# 1_ZynTra-Power.net
KiCad netlist of a schematic drawn in Altium Designer
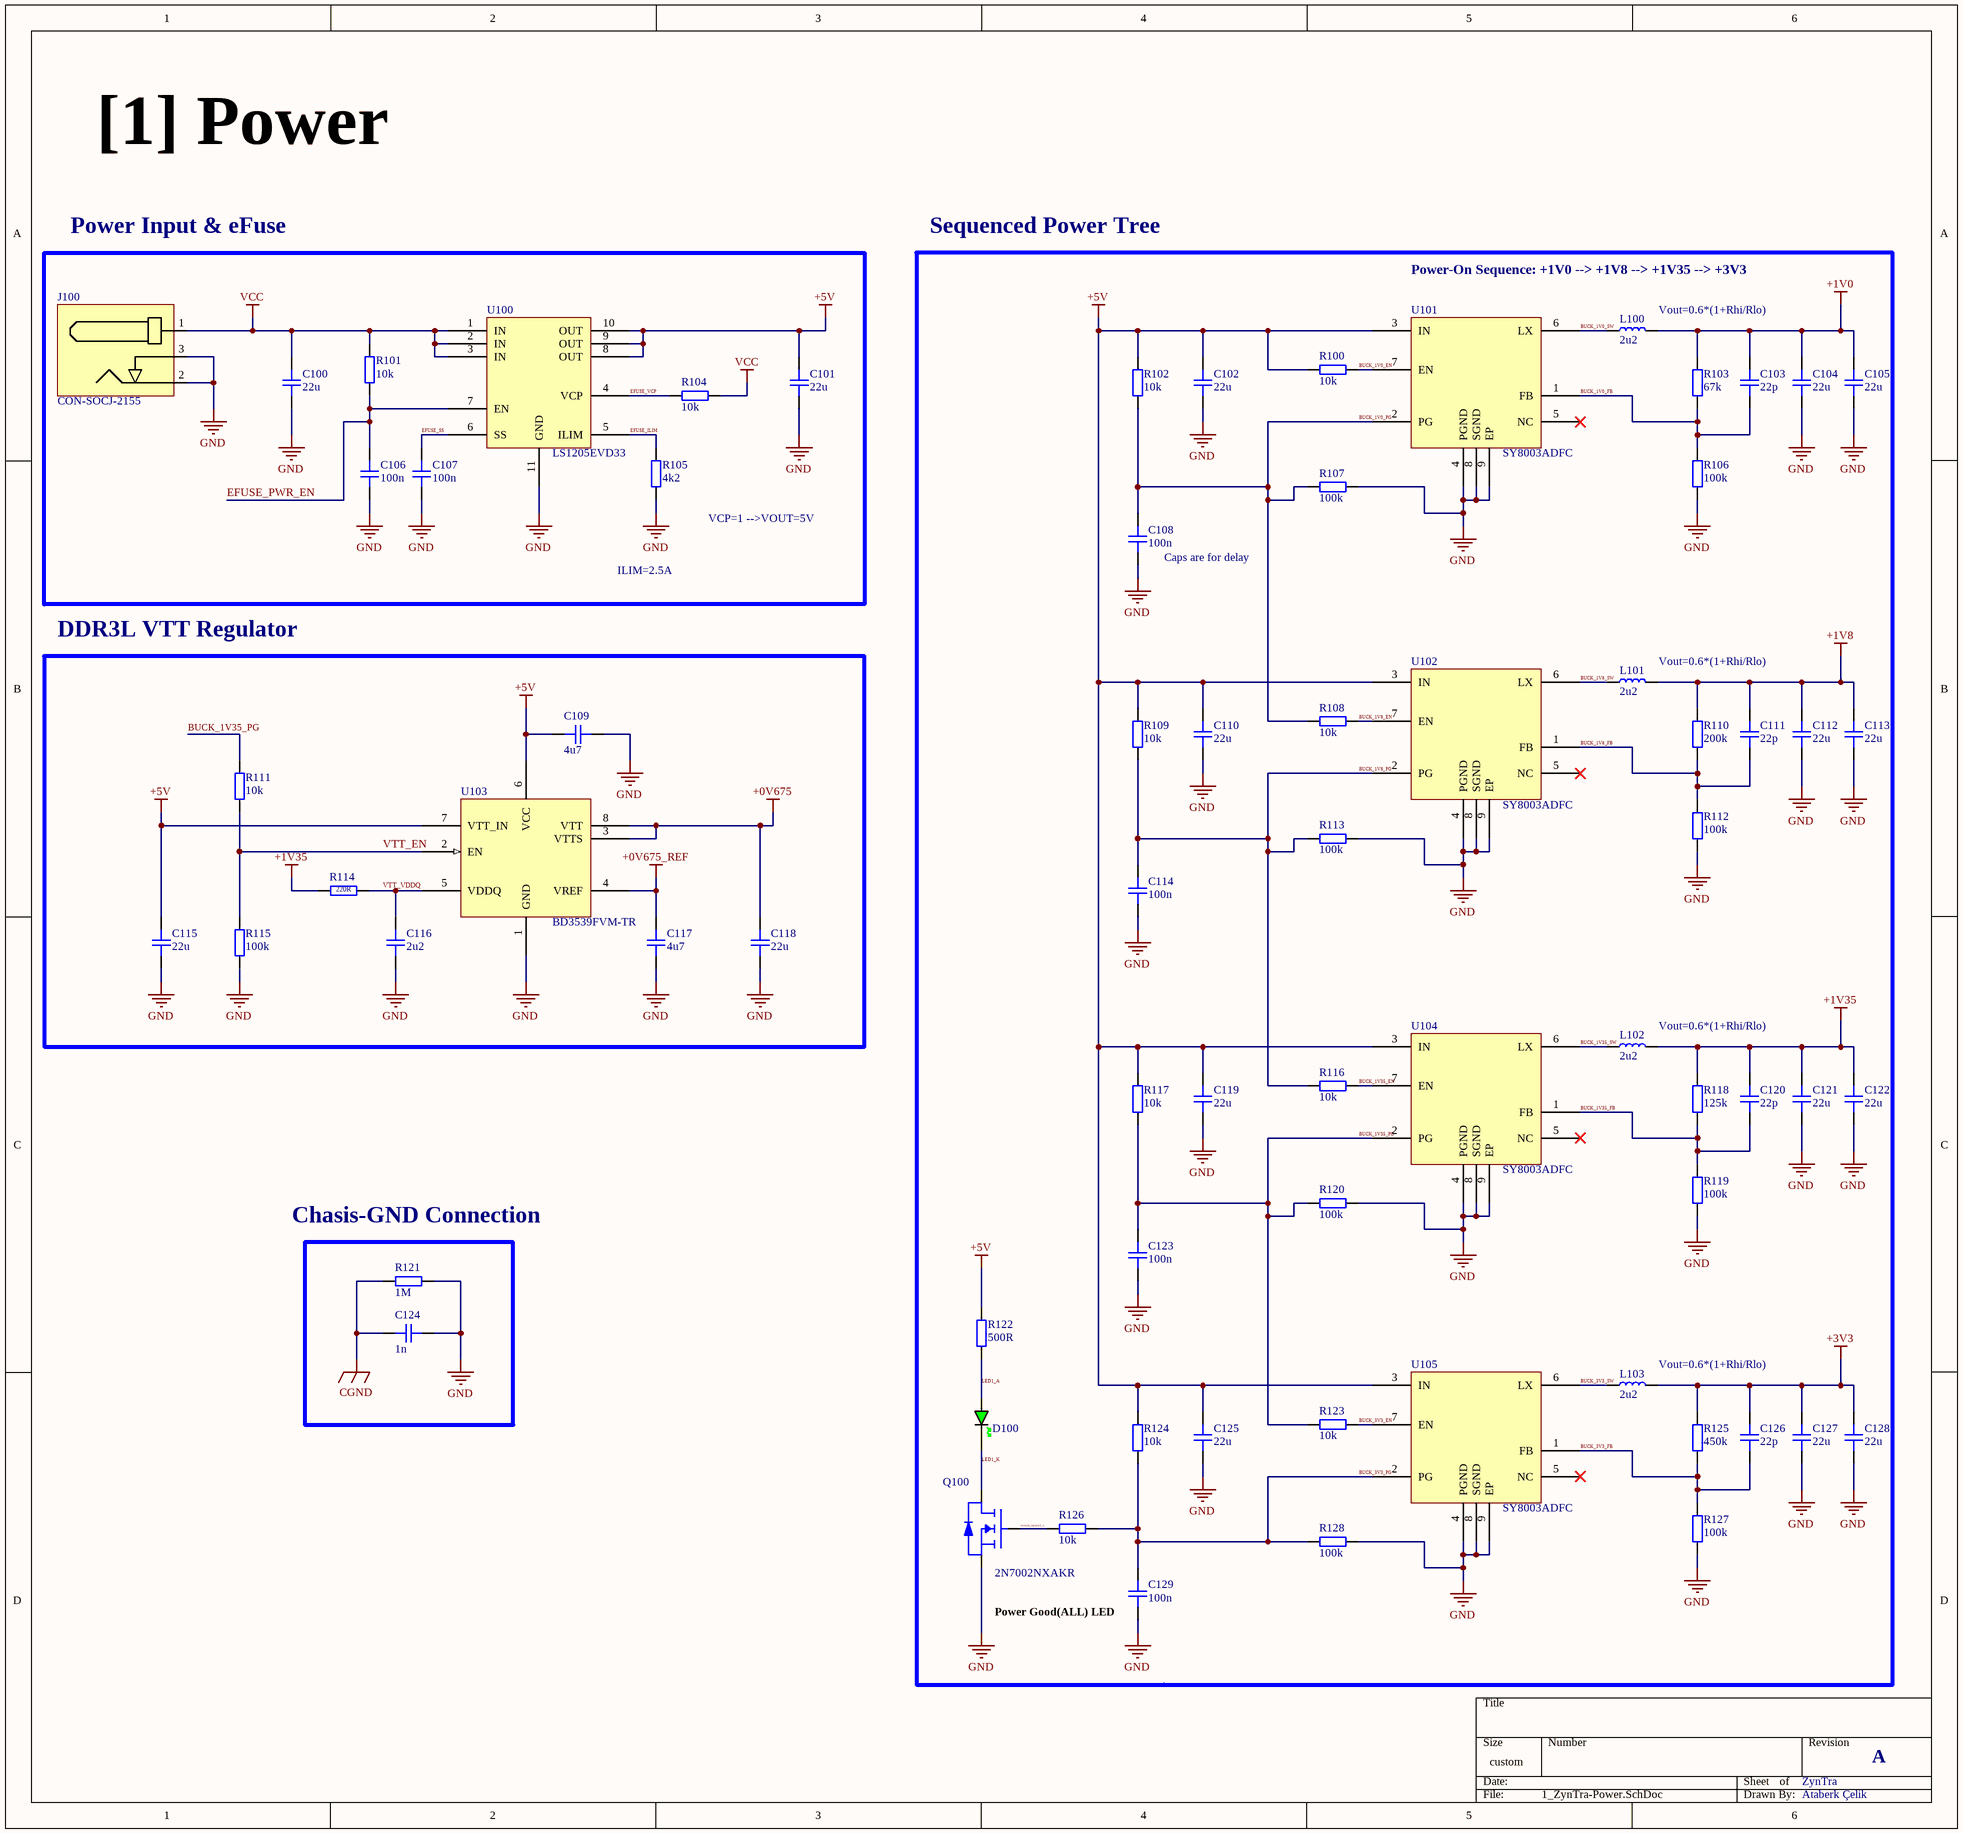
[diagram p0: 1_ZynTra-Power.SchDoc]

(export (version "E")
  (design (tool "Eeschema 10.0.6"))
  (components
    (comp (ref "C100")
      (value "22u")
      (footprint "CAP_1206")
      (description "Capacitor SMD 1206")
      (libsource (lib "Schematic-Lib-PhilsLab") (part "CAP_1206"))
    )
    (comp (ref "C101")
      (value "22u")
      (footprint "CAP_1206")
      (description "Capacitor SMD 1206")
      (libsource (lib "Schematic-Lib-PhilsLab") (part "CAP_1206"))
    )
    (comp (ref "C102")
      (value "22u")
      (footprint "CAP_1206")
      (description "Capacitor SMD 1206")
      (libsource (lib "Schematic-Lib-PhilsLab") (part "CAP_1206"))
    )
    (comp (ref "C103")
      (value "22p")
      (footprint "CAP_0201")
      (description "Capacitor SMD 0201")
      (libsource (lib "Schematic-Lib-PhilsLab") (part "CAP_0201"))
    )
    (comp (ref "C104")
      (value "22u")
      (footprint "CAP_1206")
      (description "Capacitor SMD 1206")
      (libsource (lib "Schematic-Lib-PhilsLab") (part "CAP_1206"))
    )
    (comp (ref "C105")
      (value "22u")
      (footprint "CAP_1206")
      (description "Capacitor SMD 1206")
      (libsource (lib "Schematic-Lib-PhilsLab") (part "CAP_1206"))
    )
    (comp (ref "C106")
      (value "100n")
      (footprint "CAP_0402")
      (description "Capacitor SMD 0402")
      (libsource (lib "Schematic-Lib-PhilsLab") (part "CAP_0402"))
    )
    (comp (ref "C107")
      (value "100n")
      (footprint "CAP_0402")
      (description "Capacitor SMD 0402")
      (libsource (lib "Schematic-Lib-PhilsLab") (part "CAP_0402"))
    )
    (comp (ref "C108")
      (value "100n")
      (footprint "CAP_0402")
      (description "Capacitor SMD 0402")
      (libsource (lib "Schematic-Lib-PhilsLab") (part "CAP_0402"))
    )
    (comp (ref "C109")
      (value "4u7")
      (footprint "CAP_0402")
      (description "Capacitor SMD 0402")
      (libsource (lib "Schematic-Lib-PhilsLab") (part "CAP_0402"))
    )
    (comp (ref "C110")
      (value "22u")
      (footprint "CAP_1206")
      (description "Capacitor SMD 1206")
      (libsource (lib "Schematic-Lib-PhilsLab") (part "CAP_1206"))
    )
    (comp (ref "C111")
      (value "22p")
      (footprint "CAP_0201")
      (description "Capacitor SMD 0201")
      (libsource (lib "Schematic-Lib-PhilsLab") (part "CAP_0201"))
    )
    (comp (ref "C112")
      (value "22u")
      (footprint "CAP_1206")
      (description "Capacitor SMD 1206")
      (libsource (lib "Schematic-Lib-PhilsLab") (part "CAP_1206"))
    )
    (comp (ref "C113")
      (value "22u")
      (footprint "CAP_1206")
      (description "Capacitor SMD 1206")
      (libsource (lib "Schematic-Lib-PhilsLab") (part "CAP_1206"))
    )
    (comp (ref "C114")
      (value "100n")
      (footprint "CAP_0402")
      (description "Capacitor SMD 0402")
      (libsource (lib "Schematic-Lib-PhilsLab") (part "CAP_0402"))
    )
    (comp (ref "C115")
      (value "22u")
      (footprint "CAP_1206")
      (description "Capacitor SMD 1206")
      (libsource (lib "Schematic-Lib-PhilsLab") (part "CAP_1206"))
    )
    (comp (ref "C116")
      (value "2u2")
      (footprint "CAP_0402")
      (description "Capacitor SMD 0402")
      (libsource (lib "Schematic-Lib-PhilsLab") (part "CAP_0402"))
    )
    (comp (ref "C117")
      (value "4u7")
      (footprint "CAP_0402")
      (description "Capacitor SMD 0402")
      (libsource (lib "Schematic-Lib-PhilsLab") (part "CAP_0402"))
    )
    (comp (ref "C118")
      (value "22u")
      (footprint "CAP_1206")
      (description "Capacitor SMD 1206")
      (libsource (lib "Schematic-Lib-PhilsLab") (part "CAP_1206"))
    )
    (comp (ref "C119")
      (value "22u")
      (footprint "CAP_1206")
      (description "Capacitor SMD 1206")
      (libsource (lib "Schematic-Lib-PhilsLab") (part "CAP_1206"))
    )
    (comp (ref "C120")
      (value "22p")
      (footprint "CAP_0201")
      (description "Capacitor SMD 0201")
      (libsource (lib "Schematic-Lib-PhilsLab") (part "CAP_0201"))
    )
    (comp (ref "C121")
      (value "22u")
      (footprint "CAP_1206")
      (description "Capacitor SMD 1206")
      (libsource (lib "Schematic-Lib-PhilsLab") (part "CAP_1206"))
    )
    (comp (ref "C122")
      (value "22u")
      (footprint "CAP_1206")
      (description "Capacitor SMD 1206")
      (libsource (lib "Schematic-Lib-PhilsLab") (part "CAP_1206"))
    )
    (comp (ref "C123")
      (value "100n")
      (footprint "CAP_0402")
      (description "Capacitor SMD 0402")
      (libsource (lib "Schematic-Lib-PhilsLab") (part "CAP_0402"))
    )
    (comp (ref "C124")
      (value "1n")
      (footprint "CAP_1206")
      (description "Capacitor SMD 1206")
      (libsource (lib "Schematic-Lib-PhilsLab") (part "CAP_1206"))
    )
    (comp (ref "C125")
      (value "22u")
      (footprint "CAP_1206")
      (description "Capacitor SMD 1206")
      (libsource (lib "Schematic-Lib-PhilsLab") (part "CAP_1206"))
    )
    (comp (ref "C126")
      (value "22p")
      (footprint "CAP_0201")
      (description "Capacitor SMD 0201")
      (libsource (lib "Schematic-Lib-PhilsLab") (part "CAP_0201"))
    )
    (comp (ref "C127")
      (value "22u")
      (footprint "CAP_1206")
      (description "Capacitor SMD 1206")
      (libsource (lib "Schematic-Lib-PhilsLab") (part "CAP_1206"))
    )
    (comp (ref "C128")
      (value "22u")
      (footprint "CAP_1206")
      (description "Capacitor SMD 1206")
      (libsource (lib "Schematic-Lib-PhilsLab") (part "CAP_1206"))
    )
    (comp (ref "C129")
      (value "100n")
      (footprint "CAP_0402")
      (description "Capacitor SMD 0402")
      (libsource (lib "Schematic-Lib-PhilsLab") (part "CAP_0402"))
    )
    (comp (ref "D100")
      (value "GREEN")
      (footprint "LED_0603_GREEN")
      (description "LED 0603 GREEN SMD")
      (libsource (lib "Schematic-Lib-PhilsLab") (part "LED_0603_GREEN"))
    )
    (comp (ref "J100")
      (value "CON-SOCJ-2155")
      (footprint "CON-SOCJ-2155")
      (description "DC Barrell Jack 2.1mm 30V 2.5A THT")
      (fields (field (name "MANUFACTURER") "Gravitech"))
      (libsource (lib "Schematic-Lib-PhilsLab") (part "CON-SOCJ-2155"))
    )
    (comp (ref "L100")
      (value "2u2")
      (footprint "SRP0415")
      (description "Inductor SMD 2.2uH Bourns SRP0415-2R2K")
      (fields (field (name "MANUFACTURER") "Bourns") (field (name "MANUFACTURER PART NUMBER") "SRP0415-2R2K"))
      (libsource (lib "Schematic-Lib-PhilsLab") (part "SRP0415-2R2K"))
    )
    (comp (ref "L101")
      (value "2u2")
      (footprint "SRP0415")
      (description "Inductor SMD 2.2uH Bourns SRP0415-2R2K")
      (fields (field (name "MANUFACTURER") "Bourns") (field (name "MANUFACTURER PART NUMBER") "SRP0415-2R2K"))
      (libsource (lib "Schematic-Lib-PhilsLab") (part "SRP0415-2R2K"))
    )
    (comp (ref "L102")
      (value "2u2")
      (footprint "SRP0415")
      (description "Inductor SMD 2.2uH Bourns SRP0415-2R2K")
      (fields (field (name "MANUFACTURER") "Bourns") (field (name "MANUFACTURER PART NUMBER") "SRP0415-2R2K"))
      (libsource (lib "Schematic-Lib-PhilsLab") (part "SRP0415-2R2K"))
    )
    (comp (ref "L103")
      (value "2u2")
      (footprint "SRP0415")
      (description "Inductor SMD 2.2uH Bourns SRP0415-2R2K")
      (fields (field (name "MANUFACTURER") "Bourns") (field (name "MANUFACTURER PART NUMBER") "SRP0415-2R2K"))
      (libsource (lib "Schematic-Lib-PhilsLab") (part "SRP0415-2R2K"))
    )
    (comp (ref "Q100")
      (value "2N7002NXAKR")
      (footprint "SSM3J338R,LF-SOT23-F")
      (description "MOSFET N-Channel Vds=60V Id=300mA with ESD Protection")
      (fields (field (name "MANUFACTURER") "Nexperia"))
      (libsource (lib "Schematic-Lib-PhilsLab") (part "2N7002NXAKR"))
    )
    (comp (ref "R100")
      (value "10k")
      (footprint "RES_0402")
      (description "Resistor SMD 0402")
      (libsource (lib "Schematic-Lib-PhilsLab") (part "RES_0402"))
    )
    (comp (ref "R101")
      (value "10k")
      (footprint "RES_0402")
      (description "Resistor SMD 0402")
      (libsource (lib "Schematic-Lib-PhilsLab") (part "RES_0402"))
    )
    (comp (ref "R102")
      (value "10k")
      (footprint "RES_0402")
      (description "Resistor SMD 0402")
      (libsource (lib "Schematic-Lib-PhilsLab") (part "RES_0402"))
    )
    (comp (ref "R103")
      (value "67k")
      (footprint "RES_0402")
      (description "Resistor SMD 0402")
      (libsource (lib "Schematic-Lib-PhilsLab") (part "RES_0402"))
    )
    (comp (ref "R104")
      (value "10k")
      (footprint "RES_0402")
      (description "Resistor SMD 0402")
      (libsource (lib "Schematic-Lib-PhilsLab") (part "RES_0402"))
    )
    (comp (ref "R105")
      (value "4k2")
      (footprint "RES_0402")
      (description "Resistor SMD 0402")
      (libsource (lib "Schematic-Lib-PhilsLab") (part "RES_0402"))
    )
    (comp (ref "R106")
      (value "100k")
      (footprint "RES_0402")
      (description "Resistor SMD 0402")
      (libsource (lib "Schematic-Lib-PhilsLab") (part "RES_0402"))
    )
    (comp (ref "R107")
      (value "100k")
      (footprint "RES_0402")
      (description "Resistor SMD 0402")
      (libsource (lib "Schematic-Lib-PhilsLab") (part "RES_0402"))
    )
    (comp (ref "R108")
      (value "10k")
      (footprint "RES_0402")
      (description "Resistor SMD 0402")
      (libsource (lib "Schematic-Lib-PhilsLab") (part "RES_0402"))
    )
    (comp (ref "R109")
      (value "10k")
      (footprint "RES_0402")
      (description "Resistor SMD 0402")
      (libsource (lib "Schematic-Lib-PhilsLab") (part "RES_0402"))
    )
    (comp (ref "R110")
      (value "200k")
      (footprint "RES_0402")
      (description "Resistor SMD 0402")
      (libsource (lib "Schematic-Lib-PhilsLab") (part "RES_0402"))
    )
    (comp (ref "R111")
      (value "10k")
      (footprint "RES_0402")
      (description "Resistor SMD 0402")
      (libsource (lib "Schematic-Lib-PhilsLab") (part "RES_0402"))
    )
    (comp (ref "R112")
      (value "100k")
      (footprint "RES_0402")
      (description "Resistor SMD 0402")
      (libsource (lib "Schematic-Lib-PhilsLab") (part "RES_0402"))
    )
    (comp (ref "R113")
      (value "100k")
      (footprint "RES_0402")
      (description "Resistor SMD 0402")
      (libsource (lib "Schematic-Lib-PhilsLab") (part "RES_0402"))
    )
    (comp (ref "R114")
      (value "220R")
      (footprint "RES_0402")
      (description "Resistor SMD 0402")
      (libsource (lib "Schematic-Lib-PhilsLab") (part "RES_0402"))
    )
    (comp (ref "R115")
      (value "100k")
      (footprint "RES_0402")
      (description "Resistor SMD 0402")
      (libsource (lib "Schematic-Lib-PhilsLab") (part "RES_0402"))
    )
    (comp (ref "R116")
      (value "10k")
      (footprint "RES_0402")
      (description "Resistor SMD 0402")
      (libsource (lib "Schematic-Lib-PhilsLab") (part "RES_0402"))
    )
    (comp (ref "R117")
      (value "10k")
      (footprint "RES_0402")
      (description "Resistor SMD 0402")
      (libsource (lib "Schematic-Lib-PhilsLab") (part "RES_0402"))
    )
    (comp (ref "R118")
      (value "125k")
      (footprint "RES_0402")
      (description "Resistor SMD 0402")
      (libsource (lib "Schematic-Lib-PhilsLab") (part "RES_0402"))
    )
    (comp (ref "R119")
      (value "100k")
      (footprint "RES_0402")
      (description "Resistor SMD 0402")
      (libsource (lib "Schematic-Lib-PhilsLab") (part "RES_0402"))
    )
    (comp (ref "R120")
      (value "100k")
      (footprint "RES_0402")
      (description "Resistor SMD 0402")
      (libsource (lib "Schematic-Lib-PhilsLab") (part "RES_0402"))
    )
    (comp (ref "R121")
      (value "1M")
      (footprint "RES_1206")
      (description "Resistor SMD 1206")
      (libsource (lib "Schematic-Lib-PhilsLab") (part "RES_1206"))
    )
    (comp (ref "R122")
      (value "500R")
      (footprint "RES_0402")
      (description "Resistor SMD 0402")
      (libsource (lib "Schematic-Lib-PhilsLab") (part "RES_0402"))
    )
    (comp (ref "R123")
      (value "10k")
      (footprint "RES_0402")
      (description "Resistor SMD 0402")
      (libsource (lib "Schematic-Lib-PhilsLab") (part "RES_0402"))
    )
    (comp (ref "R124")
      (value "10k")
      (footprint "RES_0402")
      (description "Resistor SMD 0402")
      (libsource (lib "Schematic-Lib-PhilsLab") (part "RES_0402"))
    )
    (comp (ref "R125")
      (value "450k")
      (footprint "RES_0402")
      (description "Resistor SMD 0402")
      (libsource (lib "Schematic-Lib-PhilsLab") (part "RES_0402"))
    )
    (comp (ref "R126")
      (value "10k")
      (footprint "RES_0402")
      (description "Resistor SMD 0402")
      (libsource (lib "Schematic-Lib-PhilsLab") (part "RES_0402"))
    )
    (comp (ref "R127")
      (value "100k")
      (footprint "RES_0402")
      (description "Resistor SMD 0402")
      (libsource (lib "Schematic-Lib-PhilsLab") (part "RES_0402"))
    )
    (comp (ref "R128")
      (value "100k")
      (footprint "RES_0402")
      (description "Resistor SMD 0402")
      (libsource (lib "Schematic-Lib-PhilsLab") (part "RES_0402"))
    )
    (comp (ref "U100")
      (value "LS1205EVD33")
      (footprint "DFN3x3_10L")
      (description "18V, 5A eFuse with Programmable Current Limit and Output Voltage Clamp")
      (fields (field (name "MANUFACTURER") "Littelfuse"))
      (libsource (lib "AtaSchLib") (part "LS1205EVD33"))
    )
    (comp (ref "U101")
      (value "SY8003ADFC")
      (footprint "DFN2x2-8")
      (description "High Efficiency 5.5V, 3A continuous, 1MHz\r\nSynchronous Step Down Regulator")
      (fields (field (name "MANUFACTURER") "Silergy"))
      (libsource (lib "AtaSchLib") (part "SY8003ADFC"))
    )
    (comp (ref "U102")
      (value "SY8003ADFC")
      (footprint "DFN2x2-8")
      (description "High Efficiency 5.5V, 3A continuous, 1MHz\r\nSynchronous Step Down Regulator")
      (fields (field (name "MANUFACTURER") "Silergy"))
      (libsource (lib "AtaSchLib") (part "SY8003ADFC"))
    )
    (comp (ref "U103")
      (value "BD3539FVM-TR")
      (footprint "MSOP-8, 4x2.9mm")
      (description "1.0V to 5.5V, 1A 1ch\r\nTermination Regulators for DDR-SDRAMs")
      (fields (field (name "MANUFACTURER") "ROHM Semiconductor"))
      (libsource (lib "AtaSchLib") (part "BD3539FVM-TR"))
    )
    (comp (ref "U104")
      (value "SY8003ADFC")
      (footprint "DFN2x2-8")
      (description "High Efficiency 5.5V, 3A continuous, 1MHz\r\nSynchronous Step Down Regulator")
      (fields (field (name "MANUFACTURER") "Silergy"))
      (libsource (lib "AtaSchLib") (part "SY8003ADFC"))
    )
    (comp (ref "U105")
      (value "SY8003ADFC")
      (footprint "DFN2x2-8")
      (description "High Efficiency 5.5V, 3A continuous, 1MHz\r\nSynchronous Step Down Regulator")
      (fields (field (name "MANUFACTURER") "Silergy"))
      (libsource (lib "AtaSchLib") (part "SY8003ADFC"))
    )
  )
  (nets
    (net (code "1") (name "+0V675") (class "Default")
      (node (ref "C118") (pin "2") (pinfunction "2_2") (pintype "passive"))
      (node (ref "U103") (pin "3") (pinfunction "VTTS_3") (pintype "power_in"))
      (node (ref "U103") (pin "8") (pinfunction "VTT_8") (pintype "power_in"))
    )
    (net (code "2") (name "+0V675_REF") (class "Default")
      (node (ref "C117") (pin "2") (pinfunction "2_2") (pintype "passive"))
      (node (ref "U103") (pin "4") (pinfunction "VREF_4") (pintype "power_in"))
    )
    (net (code "3") (name "+1V0") (class "Default")
      (node (ref "C103") (pin "2") (pinfunction "2_2") (pintype "passive"))
      (node (ref "C104") (pin "2") (pinfunction "2_2") (pintype "passive"))
      (node (ref "C105") (pin "2") (pinfunction "2_2") (pintype "passive"))
      (node (ref "L100") (pin "2") (pinfunction "2_2") (pintype "passive"))
      (node (ref "R103") (pin "1") (pinfunction "1_1") (pintype "passive"))
    )
    (net (code "4") (name "+1V8") (class "Default")
      (node (ref "C111") (pin "2") (pinfunction "2_2") (pintype "passive"))
      (node (ref "C112") (pin "2") (pinfunction "2_2") (pintype "passive"))
      (node (ref "C113") (pin "2") (pinfunction "2_2") (pintype "passive"))
      (node (ref "L101") (pin "2") (pinfunction "2_2") (pintype "passive"))
      (node (ref "R110") (pin "1") (pinfunction "1_1") (pintype "passive"))
    )
    (net (code "5") (name "+1V35") (class "Default")
      (node (ref "C120") (pin "2") (pinfunction "2_2") (pintype "passive"))
      (node (ref "C121") (pin "2") (pinfunction "2_2") (pintype "passive"))
      (node (ref "C122") (pin "2") (pinfunction "2_2") (pintype "passive"))
      (node (ref "L102") (pin "2") (pinfunction "2_2") (pintype "passive"))
      (node (ref "R114") (pin "2") (pinfunction "2_2") (pintype "passive"))
      (node (ref "R118") (pin "1") (pinfunction "1_1") (pintype "passive"))
    )
    (net (code "6") (name "+3V3") (class "Default")
      (node (ref "C126") (pin "2") (pinfunction "2_2") (pintype "passive"))
      (node (ref "C127") (pin "2") (pinfunction "2_2") (pintype "passive"))
      (node (ref "C128") (pin "2") (pinfunction "2_2") (pintype "passive"))
      (node (ref "L103") (pin "2") (pinfunction "2_2") (pintype "passive"))
      (node (ref "R125") (pin "1") (pinfunction "1_1") (pintype "passive"))
    )
    (net (code "7") (name "+5V") (class "Default")
      (node (ref "C101") (pin "2") (pinfunction "2_2") (pintype "passive"))
      (node (ref "C102") (pin "2") (pinfunction "2_2") (pintype "passive"))
      (node (ref "C109") (pin "2") (pinfunction "2_2") (pintype "passive"))
      (node (ref "C110") (pin "2") (pinfunction "2_2") (pintype "passive"))
      (node (ref "C115") (pin "2") (pinfunction "2_2") (pintype "passive"))
      (node (ref "C119") (pin "2") (pinfunction "2_2") (pintype "passive"))
      (node (ref "C125") (pin "2") (pinfunction "2_2") (pintype "passive"))
      (node (ref "R100") (pin "2") (pinfunction "2_2") (pintype "passive"))
      (node (ref "R102") (pin "1") (pinfunction "1_1") (pintype "passive"))
      (node (ref "R109") (pin "1") (pinfunction "1_1") (pintype "passive"))
      (node (ref "R117") (pin "1") (pinfunction "1_1") (pintype "passive"))
      (node (ref "R122") (pin "1") (pinfunction "1_1") (pintype "passive"))
      (node (ref "R124") (pin "1") (pinfunction "1_1") (pintype "passive"))
      (node (ref "U100") (pin "10") (pinfunction "OUT_10") (pintype "power_in"))
      (node (ref "U100") (pin "8") (pinfunction "OUT_8") (pintype "power_in"))
      (node (ref "U100") (pin "9") (pinfunction "OUT_9") (pintype "power_in"))
      (node (ref "U101") (pin "3") (pinfunction "IN_3") (pintype "power_in"))
      (node (ref "U102") (pin "3") (pinfunction "IN_3") (pintype "power_in"))
      (node (ref "U103") (pin "6") (pinfunction "VCC_6") (pintype "power_in"))
      (node (ref "U103") (pin "7") (pinfunction "VTT_IN_7") (pintype "power_in"))
      (node (ref "U104") (pin "3") (pinfunction "IN_3") (pintype "power_in"))
      (node (ref "U105") (pin "3") (pinfunction "IN_3") (pintype "power_in"))
    )
    (net (code "8") (name "/BUCK_1V0_EN") (class "Default")
      (node (ref "R100") (pin "1") (pinfunction "1_1") (pintype "passive"))
      (node (ref "U101") (pin "7") (pinfunction "EN_7") (pintype "power_in"))
    )
    (net (code "9") (name "/BUCK_1V0_FB") (class "Default")
      (node (ref "C103") (pin "1") (pinfunction "1_1") (pintype "passive"))
      (node (ref "R103") (pin "2") (pinfunction "2_2") (pintype "passive"))
      (node (ref "R106") (pin "1") (pinfunction "1_1") (pintype "passive"))
      (node (ref "U101") (pin "1") (pinfunction "FB_1") (pintype "power_in"))
    )
    (net (code "10") (name "/BUCK_1V0_PG") (class "Default")
      (node (ref "C108") (pin "2") (pinfunction "2_2") (pintype "passive"))
      (node (ref "R102") (pin "2") (pinfunction "2_2") (pintype "passive"))
      (node (ref "R107") (pin "1") (pinfunction "1_1") (pintype "passive"))
      (node (ref "R108") (pin "2") (pinfunction "2_2") (pintype "passive"))
      (node (ref "U101") (pin "2") (pinfunction "PG_2") (pintype "power_in"))
    )
    (net (code "11") (name "/BUCK_1V0_SW") (class "Default")
      (node (ref "L100") (pin "1") (pinfunction "1_1") (pintype "passive"))
      (node (ref "U101") (pin "6") (pinfunction "LX_6") (pintype "power_in"))
    )
    (net (code "12") (name "/BUCK_1V8_EN") (class "Default")
      (node (ref "R108") (pin "1") (pinfunction "1_1") (pintype "passive"))
      (node (ref "U102") (pin "7") (pinfunction "EN_7") (pintype "power_in"))
    )
    (net (code "13") (name "/BUCK_1V8_FB") (class "Default")
      (node (ref "C111") (pin "1") (pinfunction "1_1") (pintype "passive"))
      (node (ref "R110") (pin "2") (pinfunction "2_2") (pintype "passive"))
      (node (ref "R112") (pin "1") (pinfunction "1_1") (pintype "passive"))
      (node (ref "U102") (pin "1") (pinfunction "FB_1") (pintype "power_in"))
    )
    (net (code "14") (name "/BUCK_1V8_PG") (class "Default")
      (node (ref "C114") (pin "2") (pinfunction "2_2") (pintype "passive"))
      (node (ref "R109") (pin "2") (pinfunction "2_2") (pintype "passive"))
      (node (ref "R113") (pin "1") (pinfunction "1_1") (pintype "passive"))
      (node (ref "R116") (pin "2") (pinfunction "2_2") (pintype "passive"))
      (node (ref "U102") (pin "2") (pinfunction "PG_2") (pintype "power_in"))
    )
    (net (code "15") (name "/BUCK_1V8_SW") (class "Default")
      (node (ref "L101") (pin "1") (pinfunction "1_1") (pintype "passive"))
      (node (ref "U102") (pin "6") (pinfunction "LX_6") (pintype "power_in"))
    )
    (net (code "16") (name "/BUCK_1V35_EN") (class "Default")
      (node (ref "R116") (pin "1") (pinfunction "1_1") (pintype "passive"))
      (node (ref "U104") (pin "7") (pinfunction "EN_7") (pintype "power_in"))
    )
    (net (code "17") (name "/BUCK_1V35_FB") (class "Default")
      (node (ref "C120") (pin "1") (pinfunction "1_1") (pintype "passive"))
      (node (ref "R118") (pin "2") (pinfunction "2_2") (pintype "passive"))
      (node (ref "R119") (pin "1") (pinfunction "1_1") (pintype "passive"))
      (node (ref "U104") (pin "1") (pinfunction "FB_1") (pintype "power_in"))
    )
    (net (code "18") (name "/BUCK_1V35_PG") (class "Default")
      (node (ref "C123") (pin "2") (pinfunction "2_2") (pintype "passive"))
      (node (ref "R111") (pin "1") (pinfunction "1_1") (pintype "passive"))
      (node (ref "R117") (pin "2") (pinfunction "2_2") (pintype "passive"))
      (node (ref "R120") (pin "1") (pinfunction "1_1") (pintype "passive"))
      (node (ref "R123") (pin "2") (pinfunction "2_2") (pintype "passive"))
      (node (ref "U104") (pin "2") (pinfunction "PG_2") (pintype "power_in"))
    )
    (net (code "19") (name "/BUCK_1V35_SW") (class "Default")
      (node (ref "L102") (pin "1") (pinfunction "1_1") (pintype "passive"))
      (node (ref "U104") (pin "6") (pinfunction "LX_6") (pintype "power_in"))
    )
    (net (code "20") (name "/BUCK_3V3_EN") (class "Default")
      (node (ref "R123") (pin "1") (pinfunction "1_1") (pintype "passive"))
      (node (ref "U105") (pin "7") (pinfunction "EN_7") (pintype "power_in"))
    )
    (net (code "21") (name "/BUCK_3V3_FB") (class "Default")
      (node (ref "C126") (pin "1") (pinfunction "1_1") (pintype "passive"))
      (node (ref "R125") (pin "2") (pinfunction "2_2") (pintype "passive"))
      (node (ref "R127") (pin "1") (pinfunction "1_1") (pintype "passive"))
      (node (ref "U105") (pin "1") (pinfunction "FB_1") (pintype "power_in"))
    )
    (net (code "22") (name "/BUCK_3V3_PG") (class "Default")
      (node (ref "C129") (pin "2") (pinfunction "2_2") (pintype "passive"))
      (node (ref "R124") (pin "2") (pinfunction "2_2") (pintype "passive"))
      (node (ref "R126") (pin "2") (pinfunction "2_2") (pintype "passive"))
      (node (ref "R128") (pin "1") (pinfunction "1_1") (pintype "passive"))
      (node (ref "U105") (pin "2") (pinfunction "PG_2") (pintype "power_in"))
    )
    (net (code "23") (name "/BUCK_3V3_SW") (class "Default")
      (node (ref "L103") (pin "1") (pinfunction "1_1") (pintype "passive"))
      (node (ref "U105") (pin "6") (pinfunction "LX_6") (pintype "power_in"))
    )
    (net (code "24") (name "/EFUSE_ILIM") (class "Default")
      (node (ref "R105") (pin "2") (pinfunction "2_2") (pintype "passive"))
      (node (ref "U100") (pin "5") (pinfunction "ILIM_5") (pintype "power_in"))
    )
    (net (code "25") (name "/EFUSE_PWR_EN") (class "Default")
      (node (ref "C106") (pin "2") (pinfunction "2_2") (pintype "passive"))
      (node (ref "R101") (pin "1") (pinfunction "1_1") (pintype "passive"))
      (node (ref "U100") (pin "7") (pinfunction "EN_7") (pintype "power_in"))
    )
    (net (code "26") (name "/EFUSE_SS") (class "Default")
      (node (ref "C107") (pin "2") (pinfunction "2_2") (pintype "passive"))
      (node (ref "U100") (pin "6") (pinfunction "SS_6") (pintype "power_in"))
    )
    (net (code "27") (name "/EFUSE_VCP") (class "Default")
      (node (ref "R104") (pin "2") (pinfunction "2_2") (pintype "passive"))
      (node (ref "U100") (pin "4") (pinfunction "VCP_4") (pintype "power_in"))
    )
    (net (code "28") (name "/LED1_A") (class "Default")
      (node (ref "D100") (pin "A") (pinfunction "A_A") (pintype "passive"))
      (node (ref "R122") (pin "2") (pinfunction "2_2") (pintype "passive"))
    )
    (net (code "29") (name "/LED1_K") (class "Default")
      (node (ref "D100") (pin "K") (pinfunction "K_K") (pintype "passive"))
      (node (ref "Q100") (pin "D") (pinfunction "D_D") (pintype "passive"))
    )
    (net (code "30") (name "/POWER_MOSFET_G") (class "Default")
      (node (ref "Q100") (pin "G") (pinfunction "G_G") (pintype "passive"))
      (node (ref "R126") (pin "1") (pinfunction "1_1") (pintype "passive"))
    )
    (net (code "31") (name "/VTT_EN") (class "Default")
      (node (ref "R111") (pin "2") (pinfunction "2_2") (pintype "passive"))
      (node (ref "R115") (pin "2") (pinfunction "2_2") (pintype "passive"))
      (node (ref "U103") (pin "2") (pinfunction "EN_2") (pintype "input"))
    )
    (net (code "32") (name "/VTT_VDDQ") (class "Default")
      (node (ref "C116") (pin "2") (pinfunction "2_2") (pintype "passive"))
      (node (ref "R114") (pin "1") (pinfunction "1_1") (pintype "passive"))
      (node (ref "U103") (pin "5") (pinfunction "VDDQ_5") (pintype "power_in"))
    )
    (net (code "33") (name "CGND") (class "Default")
      (node (ref "C124") (pin "1") (pinfunction "1_1") (pintype "passive"))
      (node (ref "R121") (pin "1") (pinfunction "1_1") (pintype "passive"))
    )
    (net (code "34") (name "GND") (class "Default")
      (node (ref "C100") (pin "1") (pinfunction "1_1") (pintype "passive"))
      (node (ref "C101") (pin "1") (pinfunction "1_1") (pintype "passive"))
      (node (ref "C102") (pin "1") (pinfunction "1_1") (pintype "passive"))
      (node (ref "C104") (pin "1") (pinfunction "1_1") (pintype "passive"))
      (node (ref "C105") (pin "1") (pinfunction "1_1") (pintype "passive"))
      (node (ref "C106") (pin "1") (pinfunction "1_1") (pintype "passive"))
      (node (ref "C107") (pin "1") (pinfunction "1_1") (pintype "passive"))
      (node (ref "C108") (pin "1") (pinfunction "1_1") (pintype "passive"))
      (node (ref "C109") (pin "1") (pinfunction "1_1") (pintype "passive"))
      (node (ref "C110") (pin "1") (pinfunction "1_1") (pintype "passive"))
      (node (ref "C112") (pin "1") (pinfunction "1_1") (pintype "passive"))
      (node (ref "C113") (pin "1") (pinfunction "1_1") (pintype "passive"))
      (node (ref "C114") (pin "1") (pinfunction "1_1") (pintype "passive"))
      (node (ref "C115") (pin "1") (pinfunction "1_1") (pintype "passive"))
      (node (ref "C116") (pin "1") (pinfunction "1_1") (pintype "passive"))
      (node (ref "C117") (pin "1") (pinfunction "1_1") (pintype "passive"))
      (node (ref "C118") (pin "1") (pinfunction "1_1") (pintype "passive"))
      (node (ref "C119") (pin "1") (pinfunction "1_1") (pintype "passive"))
      (node (ref "C121") (pin "1") (pinfunction "1_1") (pintype "passive"))
      (node (ref "C122") (pin "1") (pinfunction "1_1") (pintype "passive"))
      (node (ref "C123") (pin "1") (pinfunction "1_1") (pintype "passive"))
      (node (ref "C124") (pin "2") (pinfunction "2_2") (pintype "passive"))
      (node (ref "C125") (pin "1") (pinfunction "1_1") (pintype "passive"))
      (node (ref "C127") (pin "1") (pinfunction "1_1") (pintype "passive"))
      (node (ref "C128") (pin "1") (pinfunction "1_1") (pintype "passive"))
      (node (ref "C129") (pin "1") (pinfunction "1_1") (pintype "passive"))
      (node (ref "J100") (pin "2") (pinfunction "2_2") (pintype "passive"))
      (node (ref "J100") (pin "3") (pinfunction "3_3") (pintype "passive"))
      (node (ref "Q100") (pin "S") (pinfunction "S_S") (pintype "passive"))
      (node (ref "R105") (pin "1") (pinfunction "1_1") (pintype "passive"))
      (node (ref "R106") (pin "2") (pinfunction "2_2") (pintype "passive"))
      (node (ref "R107") (pin "2") (pinfunction "2_2") (pintype "passive"))
      (node (ref "R112") (pin "2") (pinfunction "2_2") (pintype "passive"))
      (node (ref "R113") (pin "2") (pinfunction "2_2") (pintype "passive"))
      (node (ref "R115") (pin "1") (pinfunction "1_1") (pintype "passive"))
      (node (ref "R119") (pin "2") (pinfunction "2_2") (pintype "passive"))
      (node (ref "R120") (pin "2") (pinfunction "2_2") (pintype "passive"))
      (node (ref "R121") (pin "2") (pinfunction "2_2") (pintype "passive"))
      (node (ref "R127") (pin "2") (pinfunction "2_2") (pintype "passive"))
      (node (ref "R128") (pin "2") (pinfunction "2_2") (pintype "passive"))
      (node (ref "U100") (pin "11") (pinfunction "GND_11") (pintype "power_in"))
      (node (ref "U101") (pin "4") (pinfunction "PGND_4") (pintype "power_in"))
      (node (ref "U101") (pin "8") (pinfunction "SGND_8") (pintype "power_in"))
      (node (ref "U101") (pin "9") (pinfunction "EP_9") (pintype "power_in"))
      (node (ref "U102") (pin "4") (pinfunction "PGND_4") (pintype "power_in"))
      (node (ref "U102") (pin "8") (pinfunction "SGND_8") (pintype "power_in"))
      (node (ref "U102") (pin "9") (pinfunction "EP_9") (pintype "power_in"))
      (node (ref "U103") (pin "1") (pinfunction "GND_1") (pintype "power_in"))
      (node (ref "U104") (pin "4") (pinfunction "PGND_4") (pintype "power_in"))
      (node (ref "U104") (pin "8") (pinfunction "SGND_8") (pintype "power_in"))
      (node (ref "U104") (pin "9") (pinfunction "EP_9") (pintype "power_in"))
      (node (ref "U105") (pin "4") (pinfunction "PGND_4") (pintype "power_in"))
      (node (ref "U105") (pin "8") (pinfunction "SGND_8") (pintype "power_in"))
      (node (ref "U105") (pin "9") (pinfunction "EP_9") (pintype "power_in"))
    )
    (net (code "35") (name "VCC") (class "Default")
      (node (ref "C100") (pin "2") (pinfunction "2_2") (pintype "passive"))
      (node (ref "J100") (pin "1") (pinfunction "1_1") (pintype "passive"))
      (node (ref "R101") (pin "2") (pinfunction "2_2") (pintype "passive"))
      (node (ref "R104") (pin "1") (pinfunction "1_1") (pintype "passive"))
      (node (ref "U100") (pin "1") (pinfunction "IN_1") (pintype "power_in"))
      (node (ref "U100") (pin "2") (pinfunction "IN_2") (pintype "power_in"))
      (node (ref "U100") (pin "3") (pinfunction "IN_3") (pintype "power_in"))
    )
    (net (code "36") (name "unconnected-(U101-NC-Pad5)") (class "Default")
      (node (ref "U101") (pin "5") (pinfunction "NC_5") (pintype "power_in+no_connect"))
    )
    (net (code "37") (name "unconnected-(U102-NC-Pad5)") (class "Default")
      (node (ref "U102") (pin "5") (pinfunction "NC_5") (pintype "power_in+no_connect"))
    )
    (net (code "38") (name "unconnected-(U104-NC-Pad5)") (class "Default")
      (node (ref "U104") (pin "5") (pinfunction "NC_5") (pintype "power_in+no_connect"))
    )
    (net (code "39") (name "unconnected-(U105-NC-Pad5)") (class "Default")
      (node (ref "U105") (pin "5") (pinfunction "NC_5") (pintype "power_in+no_connect"))
    )
  )
)
